# USB-TTL.net
KiCad netlist of a schematic drawn in Altium Designer
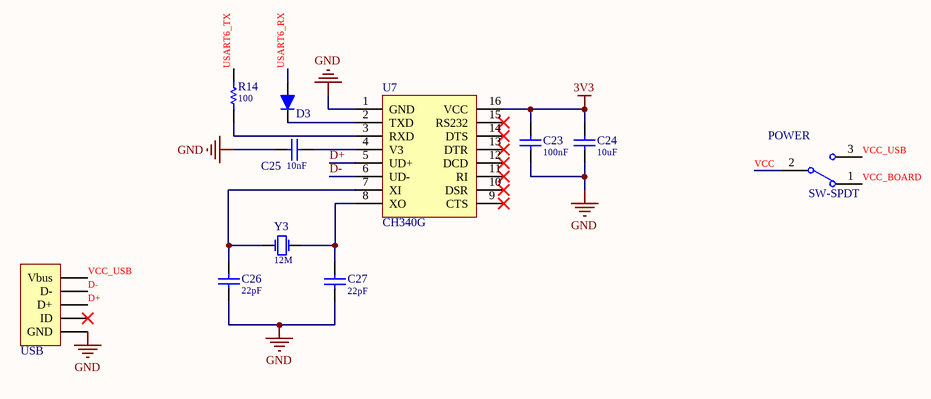
[diagram p0: USB-TTL.SchDoc]

(export (version "E")
  (design (tool "Eeschema 10.0.6"))
  (components
    (comp (ref "C23")
      (value "100nF")
      (footprint "C0603-L")
      (description "贴片瓷片电容")
      (fields (field (name "Comment") "Cap-S"))
      (libsource (lib "XuZhe") (part "Cap-S"))
    )
    (comp (ref "C24")
      (value "10uF")
      (footprint "C0603-L")
      (description "贴片瓷片电容")
      (fields (field (name "Comment") "Cap-S"))
      (libsource (lib "XuZhe") (part "Cap-S"))
    )
    (comp (ref "C25")
      (value "10nF")
      (footprint "C0603-L")
      (description "贴片瓷片电容")
      (fields (field (name "Comment") "Cap-S"))
      (libsource (lib "XuZhe") (part "Cap-S"))
    )
    (comp (ref "C26")
      (value "22pF")
      (footprint "C0603-L")
      (description "贴片瓷片电容")
      (fields (field (name "Comment") "Cap-S"))
      (libsource (lib "XuZhe") (part "Cap-S"))
    )
    (comp (ref "C27")
      (value "22pF")
      (footprint "C0603-L")
      (description "贴片瓷片电容")
      (fields (field (name "Comment") "Cap-S"))
      (libsource (lib "XuZhe") (part "Cap-S"))
    )
    (comp (ref "D3")
      (value "D")
      (footprint "D-SMA")
      (description "二极管")
      (libsource (lib "XuZhe") (part "Diode"))
    )
    (comp (ref "POWER")
      (value "SW-SPDT")
      (footprint "SW-SPDT")
      (description "SPDT Subminiature Toggle Switch, Right Angle Mounting, Vertical Actuation")
      (libsource (lib "XuZhe") (part "SW-SPDT"))
    )
    (comp (ref "R14")
      (value "100")
      (footprint "R0603-L")
      (description "贴片电阻")
      (fields (field (name "Comment") "R"))
      (libsource (lib "XuZhe") (part "Res"))
    )
    (comp (ref "U7")
      (value "CH340G")
      (footprint "SOP-16")
      (description "SOP16")
      (libsource (lib "XuZhe") (part "CH340G"))
    )
    (comp (ref "USB")
      (value "USB_Mini/Micro")
      (footprint "USB_Micro")
      (description "Mini/Micro USB母口")
      (libsource (lib "XuZhe") (part "USB"))
    )
    (comp (ref "Y3")
      (value "12M")
      (footprint "XTAL-PB2-DIP")
      (description "晶振")
      (fields (field (name "Comment") "XTAL"))
      (libsource (lib "XuZhe") (part "XTAL"))
    )
  )
  (nets
    (net (code "1") (name "/D+") (class "Default")
      (node (ref "U7") (pin "5") (pinfunction "UD+_5") (pintype "passive"))
      (node (ref "USB") (pin "3") (pinfunction "D+_3") (pintype "passive"))
    )
    (net (code "2") (name "/D-") (class "Default")
      (node (ref "U7") (pin "6") (pinfunction "UD-_6") (pintype "passive"))
      (node (ref "USB") (pin "2") (pinfunction "D-_2") (pintype "passive"))
    )
    (net (code "3") (name "/USART6_RX") (class "Default")
      (node (ref "D3") (pin "1") (pinfunction "1_1") (pintype "passive"))
    )
    (net (code "4") (name "/USART6_TX") (class "Default")
      (node (ref "R14") (pin "2") (pinfunction "2_2") (pintype "passive"))
    )
    (net (code "5") (name "/VCC") (class "Default")
      (node (ref "POWER") (pin "2") (pinfunction "2_2") (pintype "passive"))
    )
    (net (code "6") (name "/VCC_BOARD") (class "Default")
      (node (ref "POWER") (pin "1") (pinfunction "1_1") (pintype "passive"))
    )
    (net (code "7") (name "/VCC_USB") (class "Default")
      (node (ref "POWER") (pin "3") (pinfunction "3_3") (pintype "passive"))
      (node (ref "USB") (pin "1") (pinfunction "Vbus_1") (pintype "passive"))
    )
    (net (code "8") (name "3V3") (class "Default")
      (node (ref "C23") (pin "2") (pinfunction "2_2") (pintype "passive"))
      (node (ref "C24") (pin "2") (pinfunction "2_2") (pintype "passive"))
      (node (ref "U7") (pin "16") (pinfunction "VCC_16") (pintype "passive"))
    )
    (net (code "9") (name "GND") (class "Default")
      (node (ref "C23") (pin "1") (pinfunction "1_1") (pintype "passive"))
      (node (ref "C24") (pin "1") (pinfunction "1_1") (pintype "passive"))
      (node (ref "C25") (pin "1") (pinfunction "1_1") (pintype "passive"))
      (node (ref "C26") (pin "1") (pinfunction "1_1") (pintype "passive"))
      (node (ref "C27") (pin "1") (pinfunction "1_1") (pintype "passive"))
      (node (ref "U7") (pin "1") (pinfunction "GND_1") (pintype "passive"))
      (node (ref "USB") (pin "5") (pinfunction "GND_5") (pintype "passive"))
    )
    (net (code "10") (name "Net-(U7-RXD)") (class "Default")
      (node (ref "R14") (pin "1") (pinfunction "1_1") (pintype "passive"))
      (node (ref "U7") (pin "3") (pinfunction "RXD_3") (pintype "passive"))
    )
    (net (code "11") (name "Net-(U7-TXD)") (class "Default")
      (node (ref "D3") (pin "2") (pinfunction "2_2") (pintype "passive"))
      (node (ref "U7") (pin "2") (pinfunction "TXD_2") (pintype "passive"))
    )
    (net (code "12") (name "Net-(U7-V3)") (class "Default")
      (node (ref "C25") (pin "2") (pinfunction "2_2") (pintype "passive"))
      (node (ref "U7") (pin "4") (pinfunction "V3_4") (pintype "passive"))
    )
    (net (code "13") (name "Net-(U7-XI)") (class "Default")
      (node (ref "C26") (pin "2") (pinfunction "2_2") (pintype "passive"))
      (node (ref "U7") (pin "7") (pinfunction "XI_7") (pintype "passive"))
      (node (ref "Y3") (pin "1") (pinfunction "OSC1_1") (pintype "passive"))
    )
    (net (code "14") (name "Net-(U7-XO)") (class "Default")
      (node (ref "C27") (pin "2") (pinfunction "2_2") (pintype "passive"))
      (node (ref "U7") (pin "8") (pinfunction "XO_8") (pintype "passive"))
      (node (ref "Y3") (pin "2") (pinfunction "OSC2_2") (pintype "passive"))
    )
    (net (code "15") (name "unconnected-(U7-CTS-Pad9)") (class "Default")
      (node (ref "U7") (pin "9") (pinfunction "CTS_9") (pintype "passive+no_connect"))
    )
    (net (code "16") (name "unconnected-(U7-DCD-Pad12)") (class "Default")
      (node (ref "U7") (pin "12") (pinfunction "DCD_12") (pintype "passive+no_connect"))
    )
    (net (code "17") (name "unconnected-(U7-DSR-Pad10)") (class "Default")
      (node (ref "U7") (pin "10") (pinfunction "DSR_10") (pintype "passive+no_connect"))
    )
    (net (code "18") (name "unconnected-(U7-DTR-Pad13)") (class "Default")
      (node (ref "U7") (pin "13") (pinfunction "DTR_13") (pintype "passive+no_connect"))
    )
    (net (code "19") (name "unconnected-(U7-DTS-Pad14)") (class "Default")
      (node (ref "U7") (pin "14") (pinfunction "DTS_14") (pintype "passive+no_connect"))
    )
    (net (code "20") (name "unconnected-(U7-RI-Pad11)") (class "Default")
      (node (ref "U7") (pin "11") (pinfunction "RI_11") (pintype "passive+no_connect"))
    )
    (net (code "21") (name "unconnected-(U7-RS232-Pad15)") (class "Default")
      (node (ref "U7") (pin "15") (pinfunction "RS232_15") (pintype "passive+no_connect"))
    )
    (net (code "22") (name "unconnected-(USB-ID-Pad4)") (class "Default")
      (node (ref "USB") (pin "4") (pinfunction "ID_4") (pintype "passive+no_connect"))
    )
  )
)
